# Sch.net
KiCad netlist of a schematic drawn in Altium Designer
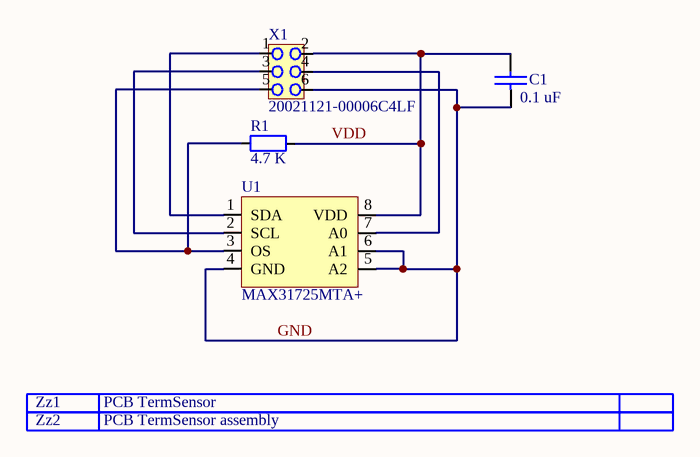
[diagram p0: Sch.SchDoc]

(export (version "E")
  (design (tool "Eeschema 10.0.6"))
  (components
    (comp (ref "C1")
      (value "0.1 uF")
      (footprint "1608[0603]")
      (description "0.1 uF, 25V, 10% , X7R,  0603 SMD MLC Capacitor")
      (fields (field (name "TOLERANCE") "10%") (field (name "MANUFACTURER") "SAMSUNG"))
      (libsource (lib "ea_Capacitors") (part "CVNF100K0603-25"))
    )
    (comp (ref "R1")
      (value "4.7 K")
      (footprint "0603")
      (description "4.7 K, 1%, 0603, SMD Resistor, Taped")
      (fields (field (name "MANUFACTURER") "YAGEO AMERICA CORPORATION") (field (name "TOLERANCE") "1%"))
      (libsource (lib "ea_Resistors") (part "RL0603K004.7-1_1"))
    )
    (comp (ref "U1")
      (value "MAX31725MTA+")
      (footprint "T833-2 Maxim")
      (description "IC TEMP SENSOR 8-TDFN")
      (fields (field (name "MANUFACTURER") "Maxim Integrated") (field (name "PARTNUM") "MAX31725MTA+-ND"))
      (libsource (lib "ea_IC_sensors") (part "MAX31725MTA+"))
    )
    (comp (ref "X1")
      (value "20021121-00006C4LF")
      (footprint "FCI_20021121-00006XXLFc")
      (description "Pin header 2X3, 1.27 mm pitch, SMD")
      (fields (field (name "MANUFACTURER") "FCI") (field (name "PARTNUM") "1865277"))
      (libsource (lib "ea_Connectors") (part "20021121-00006C4LF"))
    )
    (comp (ref "Zz1")
      (value "PCB TermSensor")
      (fields (field (name "MANUFACTURER") "Brandner") (field (name "PARTNUM") "PCB TermSensor board"))
      (libsource (lib "ea_Mechanical") (part "BOM item"))
    )
    (comp (ref "Zz2")
      (value "PCB TermSensor assembly")
      (fields (field (name "MANUFACTURER") "ESEMDA"))
      (libsource (lib "ea_Mechanical") (part "BOM item"))
    )
  )
  (nets
    (net (code "1") (name "/GND") (class "Default")
      (node (ref "C1") (pin "1") (pinfunction "1_1") (pintype "passive"))
      (node (ref "U1") (pin "4") (pinfunction "GND_4") (pintype "passive"))
      (node (ref "U1") (pin "5") (pinfunction "A2_5") (pintype "passive"))
      (node (ref "U1") (pin "6") (pinfunction "A1_6") (pintype "passive"))
      (node (ref "X1") (pin "6") (pinfunction "6_6") (pintype "passive"))
    )
    (net (code "2") (name "/VDD") (class "Default")
      (node (ref "C1") (pin "2") (pinfunction "2_2") (pintype "passive"))
      (node (ref "R1") (pin "2") (pinfunction "2_2") (pintype "passive"))
      (node (ref "U1") (pin "8") (pinfunction "VDD_8") (pintype "passive"))
      (node (ref "X1") (pin "2") (pinfunction "2_2") (pintype "passive"))
    )
    (net (code "3") (name "Net-(U1-A0)") (class "Default")
      (node (ref "U1") (pin "7") (pinfunction "A0_7") (pintype "passive"))
      (node (ref "X1") (pin "4") (pinfunction "4_4") (pintype "passive"))
    )
    (net (code "4") (name "Net-(U1-OS)") (class "Default")
      (node (ref "R1") (pin "1") (pinfunction "1_1") (pintype "passive"))
      (node (ref "U1") (pin "3") (pinfunction "OS_3") (pintype "passive"))
      (node (ref "X1") (pin "5") (pinfunction "5_5") (pintype "passive"))
    )
    (net (code "5") (name "Net-(U1-SCL)") (class "Default")
      (node (ref "U1") (pin "2") (pinfunction "SCL_2") (pintype "passive"))
      (node (ref "X1") (pin "3") (pinfunction "3_3") (pintype "passive"))
    )
    (net (code "6") (name "Net-(U1-SDA)") (class "Default")
      (node (ref "U1") (pin "1") (pinfunction "SDA_1") (pintype "passive"))
      (node (ref "X1") (pin "1") (pinfunction "1_1") (pintype "passive"))
    )
  )
)
